# NMPavi280wires.net
KiCad netlist of a schematic drawn in EAGLE
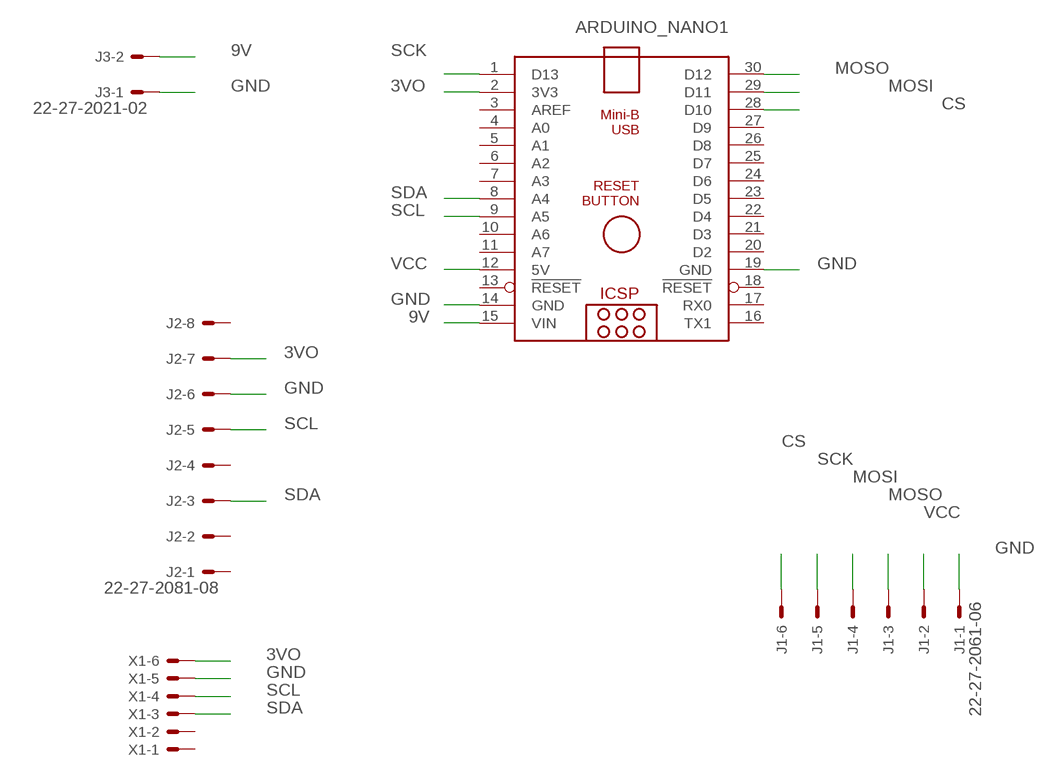
[diagram p0: schematic, sheet 1]

(export (version "E")
  (design (tool "Eeschema 10.0.6"))
  (components
    (comp (ref "ARDUINO_NANO1")
      (value "ARDUINO_NANO")
      (footprint "eagle-import:ARDUINO_NANO")
      (libsource (lib "eagle-import") (part "ARDUINO_NANO"))
    )
    (comp (ref "J1")
      (value "22-27-2061-06")
      (footprint "eagle-import:6410-06")
      (fields (field (name "MF") "MOLEX"))
      (libsource (lib "eagle-import") (part "22-?-0627-2061"))
    )
    (comp (ref "J2")
      (value "22-27-2081-08")
      (footprint "eagle-import:6410-08")
      (fields (field (name "MF") "MOLEX"))
      (libsource (lib "eagle-import") (part "22-?-0827-2081"))
    )
    (comp (ref "J3")
      (value "22-27-2021-02")
      (footprint "eagle-import:6410-02")
      (fields (field (name "MF") "MOLEX"))
      (libsource (lib "eagle-import") (part "22-?-0227-2021"))
    )
    (comp (ref "X1")
      (value "22-23-2061")
      (footprint "eagle-import:22-23-2061")
      (fields (field (name "MF") "MOLEX"))
      (libsource (lib "eagle-import") (part "22-23-2061"))
    )
  )
  (nets
    (net (code "1") (name "/3VO") (class "Default")
      (node (ref "ARDUINO_NANO1") (pin "2") (pinfunction "3V3_2") (pintype "output"))
      (node (ref "J2") (pin "7") (pinfunction "S_7") (pintype "passive"))
      (node (ref "X1") (pin "6") (pinfunction "S_6") (pintype "passive"))
    )
    (net (code "2") (name "/9V") (class "Default")
      (node (ref "ARDUINO_NANO1") (pin "15") (pinfunction "VIN_15") (pintype "power_in"))
      (node (ref "J3") (pin "2") (pinfunction "S_2") (pintype "passive"))
    )
    (net (code "3") (name "/CS") (class "Default")
      (node (ref "ARDUINO_NANO1") (pin "28") (pinfunction "D10_28") (pintype "bidirectional"))
      (node (ref "J1") (pin "6") (pinfunction "S_6") (pintype "passive"))
    )
    (net (code "4") (name "/GND") (class "Default")
      (node (ref "ARDUINO_NANO1") (pin "14") (pinfunction "GND_14") (pintype "power_in"))
      (node (ref "ARDUINO_NANO1") (pin "19") (pinfunction "GND_19") (pintype "power_in"))
      (node (ref "J1") (pin "1") (pinfunction "S_1") (pintype "passive"))
      (node (ref "J2") (pin "6") (pinfunction "S_6") (pintype "passive"))
      (node (ref "J3") (pin "1") (pinfunction "S_1") (pintype "passive"))
      (node (ref "X1") (pin "5") (pinfunction "S_5") (pintype "passive"))
    )
    (net (code "5") (name "/MOSI") (class "Default")
      (node (ref "ARDUINO_NANO1") (pin "29") (pinfunction "D11_29") (pintype "bidirectional"))
      (node (ref "J1") (pin "4") (pinfunction "S_4") (pintype "passive"))
    )
    (net (code "6") (name "/MOSO") (class "Default")
      (node (ref "ARDUINO_NANO1") (pin "30") (pinfunction "D12_30") (pintype "bidirectional"))
      (node (ref "J1") (pin "3") (pinfunction "S_3") (pintype "passive"))
    )
    (net (code "7") (name "/SCK") (class "Default")
      (node (ref "ARDUINO_NANO1") (pin "1") (pinfunction "D13_1") (pintype "bidirectional"))
      (node (ref "J1") (pin "5") (pinfunction "S_5") (pintype "passive"))
    )
    (net (code "8") (name "/SCL") (class "Default")
      (node (ref "ARDUINO_NANO1") (pin "9") (pinfunction "A5_9") (pintype "bidirectional"))
      (node (ref "J2") (pin "5") (pinfunction "S_5") (pintype "passive"))
      (node (ref "X1") (pin "4") (pinfunction "S_4") (pintype "passive"))
    )
    (net (code "9") (name "/SDA") (class "Default")
      (node (ref "ARDUINO_NANO1") (pin "8") (pinfunction "A4_8") (pintype "bidirectional"))
      (node (ref "J2") (pin "3") (pinfunction "S_3") (pintype "passive"))
      (node (ref "X1") (pin "3") (pinfunction "S_3") (pintype "passive"))
    )
    (net (code "10") (name "/VCC") (class "Default")
      (node (ref "ARDUINO_NANO1") (pin "12") (pinfunction "5V_12") (pintype "power_in"))
      (node (ref "J1") (pin "2") (pinfunction "S_2") (pintype "passive"))
    )
    (net (code "11") (name "unconnected-(ARDUINO_NANO1-A0-Pad4)") (class "Default")
      (node (ref "ARDUINO_NANO1") (pin "4") (pinfunction "A0_4") (pintype "bidirectional"))
    )
    (net (code "12") (name "unconnected-(ARDUINO_NANO1-A1-Pad5)") (class "Default")
      (node (ref "ARDUINO_NANO1") (pin "5") (pinfunction "A1_5") (pintype "bidirectional"))
    )
    (net (code "13") (name "unconnected-(ARDUINO_NANO1-A2-Pad6)") (class "Default")
      (node (ref "ARDUINO_NANO1") (pin "6") (pinfunction "A2_6") (pintype "bidirectional"))
    )
    (net (code "14") (name "unconnected-(ARDUINO_NANO1-A3-Pad7)") (class "Default")
      (node (ref "ARDUINO_NANO1") (pin "7") (pinfunction "A3_7") (pintype "bidirectional"))
    )
    (net (code "15") (name "unconnected-(ARDUINO_NANO1-A6-Pad10)") (class "Default")
      (node (ref "ARDUINO_NANO1") (pin "10") (pinfunction "A6_10") (pintype "bidirectional"))
    )
    (net (code "16") (name "unconnected-(ARDUINO_NANO1-A7-Pad11)") (class "Default")
      (node (ref "ARDUINO_NANO1") (pin "11") (pinfunction "A7_11") (pintype "bidirectional"))
    )
    (net (code "17") (name "unconnected-(ARDUINO_NANO1-AREF-Pad3)") (class "Default")
      (node (ref "ARDUINO_NANO1") (pin "3") (pinfunction "AREF_3") (pintype "input"))
    )
    (net (code "18") (name "unconnected-(ARDUINO_NANO1-D2-Pad20)") (class "Default")
      (node (ref "ARDUINO_NANO1") (pin "20") (pinfunction "D2_20") (pintype "bidirectional"))
    )
    (net (code "19") (name "unconnected-(ARDUINO_NANO1-D3-Pad21)") (class "Default")
      (node (ref "ARDUINO_NANO1") (pin "21") (pinfunction "D3_21") (pintype "bidirectional"))
    )
    (net (code "20") (name "unconnected-(ARDUINO_NANO1-D4-Pad22)") (class "Default")
      (node (ref "ARDUINO_NANO1") (pin "22") (pinfunction "D4_22") (pintype "bidirectional"))
    )
    (net (code "21") (name "unconnected-(ARDUINO_NANO1-D5-Pad23)") (class "Default")
      (node (ref "ARDUINO_NANO1") (pin "23") (pinfunction "D5_23") (pintype "bidirectional"))
    )
    (net (code "22") (name "unconnected-(ARDUINO_NANO1-D6-Pad24)") (class "Default")
      (node (ref "ARDUINO_NANO1") (pin "24") (pinfunction "D6_24") (pintype "bidirectional"))
    )
    (net (code "23") (name "unconnected-(ARDUINO_NANO1-D7-Pad25)") (class "Default")
      (node (ref "ARDUINO_NANO1") (pin "25") (pinfunction "D7_25") (pintype "bidirectional"))
    )
    (net (code "24") (name "unconnected-(ARDUINO_NANO1-D8-Pad26)") (class "Default")
      (node (ref "ARDUINO_NANO1") (pin "26") (pinfunction "D8_26") (pintype "bidirectional"))
    )
    (net (code "25") (name "unconnected-(ARDUINO_NANO1-D9-Pad27)") (class "Default")
      (node (ref "ARDUINO_NANO1") (pin "27") (pinfunction "D9_27") (pintype "bidirectional"))
    )
    (net (code "26") (name "unconnected-(ARDUINO_NANO1-RX0-Pad17)") (class "Default")
      (node (ref "ARDUINO_NANO1") (pin "17") (pinfunction "RX0_17") (pintype "bidirectional"))
    )
    (net (code "27") (name "unconnected-(ARDUINO_NANO1-TX1-Pad16)") (class "Default")
      (node (ref "ARDUINO_NANO1") (pin "16") (pinfunction "TX1_16") (pintype "bidirectional"))
    )
    (net (code "28") (name "unconnected-(ARDUINO_NANO1-~{RESET}-Pad13)") (class "Default")
      (node (ref "ARDUINO_NANO1") (pin "13") (pinfunction "~{RESET}_13") (pintype "input"))
    )
    (net (code "29") (name "unconnected-(ARDUINO_NANO1-~{RESET}-Pad18)") (class "Default")
      (node (ref "ARDUINO_NANO1") (pin "18") (pinfunction "~{RESET}_18") (pintype "input"))
    )
    (net (code "30") (name "unconnected-(J2A-S-Pad1)") (class "Default")
      (node (ref "J2") (pin "1") (pinfunction "S_1") (pintype "passive"))
    )
    (net (code "31") (name "unconnected-(J2B-S-Pad2)") (class "Default")
      (node (ref "J2") (pin "2") (pinfunction "S_2") (pintype "passive"))
    )
    (net (code "32") (name "unconnected-(J2D-S-Pad4)") (class "Default")
      (node (ref "J2") (pin "4") (pinfunction "S_4") (pintype "passive"))
    )
    (net (code "33") (name "unconnected-(J2H-S-Pad8)") (class "Default")
      (node (ref "J2") (pin "8") (pinfunction "S_8") (pintype "passive"))
    )
    (net (code "34") (name "unconnected-(X1A-S-Pad1)") (class "Default")
      (node (ref "X1") (pin "1") (pinfunction "S_1") (pintype "passive"))
    )
    (net (code "35") (name "unconnected-(X1B-S-Pad2)") (class "Default")
      (node (ref "X1") (pin "2") (pinfunction "S_2") (pintype "passive"))
    )
  )
)
